# display.net
KiCad netlist of a schematic drawn in EAGLE
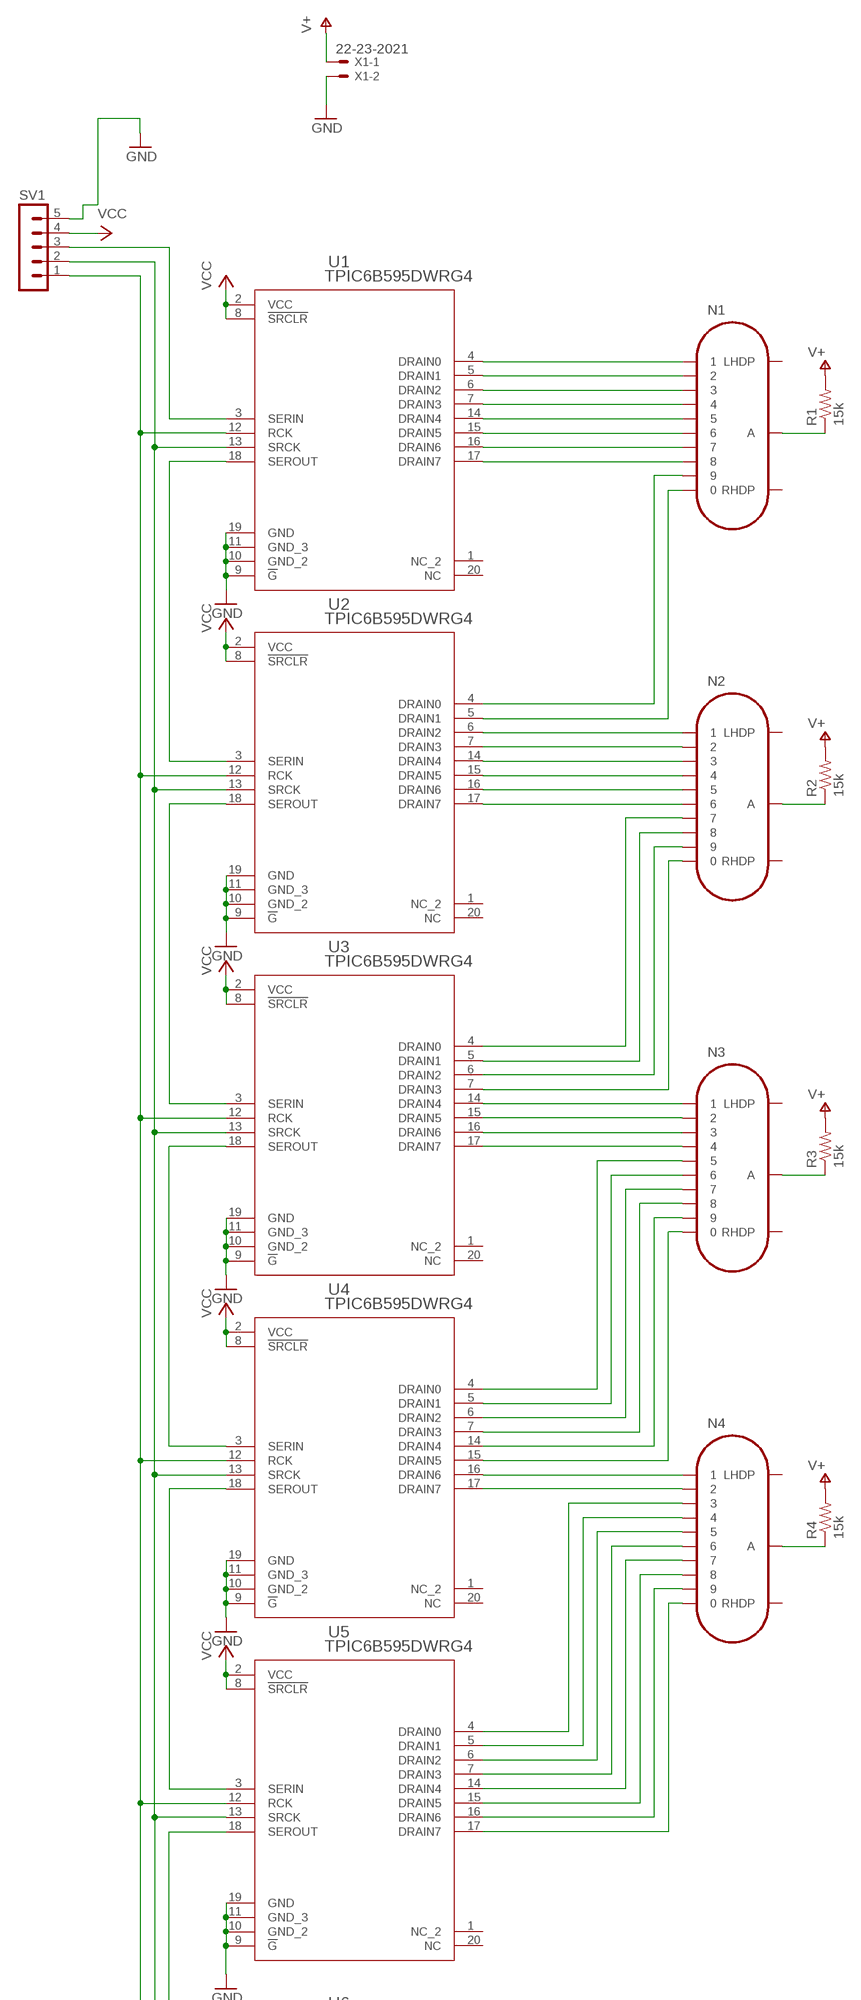
[diagram p0: schematic, sheet 1, part 1 of 2]
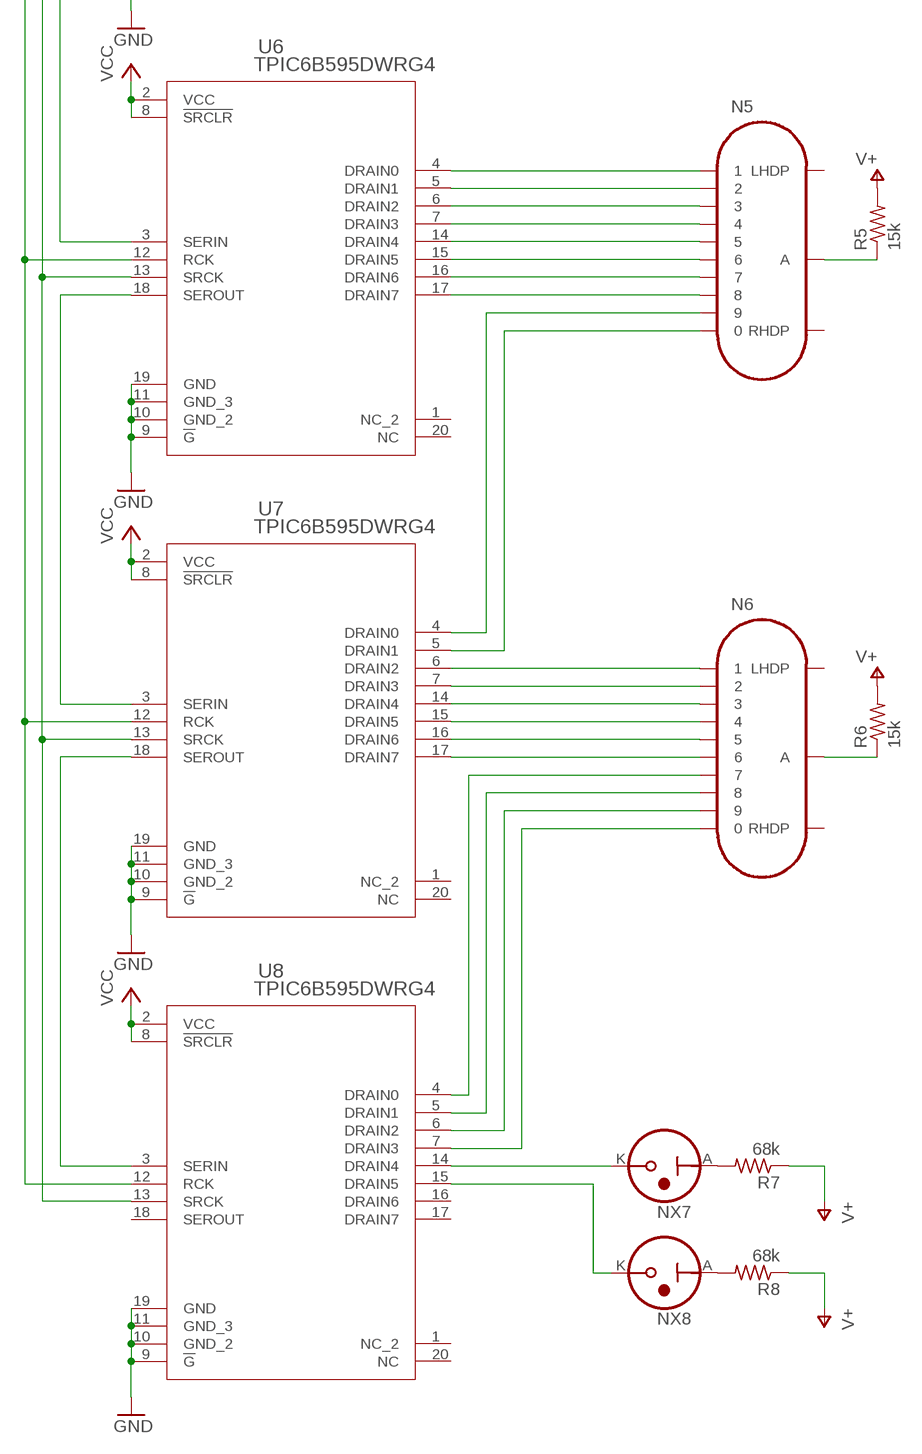
[diagram p1: schematic, sheet 1, part 2 of 2]

(export (version "E")
  (design (tool "Eeschema 10.0.6"))
  (components
    (comp (ref "N1")
      (value "IN-16")
      (footprint "eagle-import:IN-16")
      (libsource (lib "eagle-import") (part "IN-16"))
    )
    (comp (ref "N2")
      (value "IN-16")
      (footprint "eagle-import:IN-16")
      (libsource (lib "eagle-import") (part "IN-16"))
    )
    (comp (ref "N3")
      (value "IN-16")
      (footprint "eagle-import:IN-16")
      (libsource (lib "eagle-import") (part "IN-16"))
    )
    (comp (ref "N4")
      (value "IN-16")
      (footprint "eagle-import:IN-16")
      (libsource (lib "eagle-import") (part "IN-16"))
    )
    (comp (ref "N5")
      (value "IN-16")
      (footprint "eagle-import:IN-16")
      (libsource (lib "eagle-import") (part "IN-16"))
    )
    (comp (ref "N6")
      (value "IN-16")
      (footprint "eagle-import:IN-16")
      (libsource (lib "eagle-import") (part "IN-16"))
    )
    (comp (ref "NX7")
      (value "IN-3")
      (footprint "eagle-import:IN-3")
      (libsource (lib "eagle-import") (part "IN-3"))
    )
    (comp (ref "NX8")
      (value "IN-3")
      (footprint "eagle-import:IN-3")
      (libsource (lib "eagle-import") (part "IN-3"))
    )
    (comp (ref "R1")
      (value "15k")
      (footprint "eagle-import:R0805")
      (libsource (lib "eagle-import") (part "R-US_R0805"))
    )
    (comp (ref "R2")
      (value "15k")
      (footprint "eagle-import:R0805")
      (libsource (lib "eagle-import") (part "R-US_R0805"))
    )
    (comp (ref "R3")
      (value "15k")
      (footprint "eagle-import:R0805")
      (libsource (lib "eagle-import") (part "R-US_R0805"))
    )
    (comp (ref "R4")
      (value "15k")
      (footprint "eagle-import:R0805")
      (libsource (lib "eagle-import") (part "R-US_R0805"))
    )
    (comp (ref "R5")
      (value "15k")
      (footprint "eagle-import:R0805")
      (libsource (lib "eagle-import") (part "R-US_R0805"))
    )
    (comp (ref "R6")
      (value "15k")
      (footprint "eagle-import:R0805")
      (libsource (lib "eagle-import") (part "R-US_R0805"))
    )
    (comp (ref "R7")
      (value "68k")
      (footprint "eagle-import:R0805")
      (libsource (lib "eagle-import") (part "R-US_R0805"))
    )
    (comp (ref "R8")
      (value "68k")
      (footprint "eagle-import:R0805")
      (libsource (lib "eagle-import") (part "R-US_R0805"))
    )
    (comp (ref "SV1")
      (value "MA05-1")
      (footprint "eagle-import:MA05-1")
      (libsource (lib "eagle-import") (part "MA05-1"))
    )
    (comp (ref "U1")
      (value "TPIC6B595DWRG4")
      (footprint "eagle-import:DW20")
      (fields (field (name "MANUFACTURER") "Texas Instruments"))
      (libsource (lib "eagle-import") (part "TPIC6B595DWRG4"))
    )
    (comp (ref "U2")
      (value "TPIC6B595DWRG4")
      (footprint "eagle-import:DW20")
      (fields (field (name "MANUFACTURER") "Texas Instruments"))
      (libsource (lib "eagle-import") (part "TPIC6B595DWRG4"))
    )
    (comp (ref "U3")
      (value "TPIC6B595DWRG4")
      (footprint "eagle-import:DW20")
      (fields (field (name "MANUFACTURER") "Texas Instruments"))
      (libsource (lib "eagle-import") (part "TPIC6B595DWRG4"))
    )
    (comp (ref "U4")
      (value "TPIC6B595DWRG4")
      (footprint "eagle-import:DW20")
      (fields (field (name "MANUFACTURER") "Texas Instruments"))
      (libsource (lib "eagle-import") (part "TPIC6B595DWRG4"))
    )
    (comp (ref "U5")
      (value "TPIC6B595DWRG4")
      (footprint "eagle-import:DW20")
      (fields (field (name "MANUFACTURER") "Texas Instruments"))
      (libsource (lib "eagle-import") (part "TPIC6B595DWRG4"))
    )
    (comp (ref "U6")
      (value "TPIC6B595DWRG4")
      (footprint "eagle-import:DW20")
      (fields (field (name "MANUFACTURER") "Texas Instruments"))
      (libsource (lib "eagle-import") (part "TPIC6B595DWRG4"))
    )
    (comp (ref "U7")
      (value "TPIC6B595DWRG4")
      (footprint "eagle-import:DW20")
      (fields (field (name "MANUFACTURER") "Texas Instruments"))
      (libsource (lib "eagle-import") (part "TPIC6B595DWRG4"))
    )
    (comp (ref "U8")
      (value "TPIC6B595DWRG4")
      (footprint "eagle-import:DW20")
      (fields (field (name "MANUFACTURER") "Texas Instruments"))
      (libsource (lib "eagle-import") (part "TPIC6B595DWRG4"))
    )
    (comp (ref "X1")
      (value "22-23-2021")
      (footprint "eagle-import:22-23-2021")
      (fields (field (name "MF") "MOLEX"))
      (libsource (lib "eagle-import") (part "22-23-2021"))
    )
  )
  (nets
    (net (code "1") (name "GND") (class "Default")
      (node (ref "SV1") (pin "5") (pinfunction "5_5") (pintype "passive"))
      (node (ref "U1") (pin "10") (pinfunction "GND_2_10") (pintype "power_in"))
      (node (ref "U1") (pin "11") (pinfunction "GND_3_11") (pintype "power_in"))
      (node (ref "U1") (pin "19") (pinfunction "GND_19") (pintype "power_in"))
      (node (ref "U1") (pin "9") (pinfunction "~{G}_9") (pintype "input"))
      (node (ref "U2") (pin "10") (pinfunction "GND_2_10") (pintype "power_in"))
      (node (ref "U2") (pin "11") (pinfunction "GND_3_11") (pintype "power_in"))
      (node (ref "U2") (pin "19") (pinfunction "GND_19") (pintype "power_in"))
      (node (ref "U2") (pin "9") (pinfunction "~{G}_9") (pintype "input"))
      (node (ref "U3") (pin "10") (pinfunction "GND_2_10") (pintype "power_in"))
      (node (ref "U3") (pin "11") (pinfunction "GND_3_11") (pintype "power_in"))
      (node (ref "U3") (pin "19") (pinfunction "GND_19") (pintype "power_in"))
      (node (ref "U3") (pin "9") (pinfunction "~{G}_9") (pintype "input"))
      (node (ref "U4") (pin "10") (pinfunction "GND_2_10") (pintype "power_in"))
      (node (ref "U4") (pin "11") (pinfunction "GND_3_11") (pintype "power_in"))
      (node (ref "U4") (pin "19") (pinfunction "GND_19") (pintype "power_in"))
      (node (ref "U4") (pin "9") (pinfunction "~{G}_9") (pintype "input"))
      (node (ref "U5") (pin "10") (pinfunction "GND_2_10") (pintype "power_in"))
      (node (ref "U5") (pin "11") (pinfunction "GND_3_11") (pintype "power_in"))
      (node (ref "U5") (pin "19") (pinfunction "GND_19") (pintype "power_in"))
      (node (ref "U5") (pin "9") (pinfunction "~{G}_9") (pintype "input"))
      (node (ref "U6") (pin "10") (pinfunction "GND_2_10") (pintype "power_in"))
      (node (ref "U6") (pin "11") (pinfunction "GND_3_11") (pintype "power_in"))
      (node (ref "U6") (pin "19") (pinfunction "GND_19") (pintype "power_in"))
      (node (ref "U6") (pin "9") (pinfunction "~{G}_9") (pintype "input"))
      (node (ref "U7") (pin "10") (pinfunction "GND_2_10") (pintype "power_in"))
      (node (ref "U7") (pin "11") (pinfunction "GND_3_11") (pintype "power_in"))
      (node (ref "U7") (pin "19") (pinfunction "GND_19") (pintype "power_in"))
      (node (ref "U7") (pin "9") (pinfunction "~{G}_9") (pintype "input"))
      (node (ref "U8") (pin "10") (pinfunction "GND_2_10") (pintype "power_in"))
      (node (ref "U8") (pin "11") (pinfunction "GND_3_11") (pintype "power_in"))
      (node (ref "U8") (pin "19") (pinfunction "GND_19") (pintype "power_in"))
      (node (ref "U8") (pin "9") (pinfunction "~{G}_9") (pintype "input"))
      (node (ref "X1") (pin "2") (pinfunction "S_2") (pintype "passive"))
    )
    (net (code "2") (name "Net-(N1-PadA)") (class "Default")
      (node (ref "N1") (pin "A") (pinfunction "A_A") (pintype "bidirectional"))
      (node (ref "R1") (pin "1") (pinfunction "1_1") (pintype "passive"))
    )
    (net (code "3") (name "Net-(N2-PadA)") (class "Default")
      (node (ref "N2") (pin "A") (pinfunction "A_A") (pintype "bidirectional"))
      (node (ref "R2") (pin "1") (pinfunction "1_1") (pintype "passive"))
    )
    (net (code "4") (name "Net-(N3-PadA)") (class "Default")
      (node (ref "N3") (pin "A") (pinfunction "A_A") (pintype "bidirectional"))
      (node (ref "R3") (pin "1") (pinfunction "1_1") (pintype "passive"))
    )
    (net (code "5") (name "Net-(N4-PadA)") (class "Default")
      (node (ref "N4") (pin "A") (pinfunction "A_A") (pintype "bidirectional"))
      (node (ref "R4") (pin "1") (pinfunction "1_1") (pintype "passive"))
    )
    (net (code "6") (name "Net-(N5-PadA)") (class "Default")
      (node (ref "N5") (pin "A") (pinfunction "A_A") (pintype "bidirectional"))
      (node (ref "R5") (pin "1") (pinfunction "1_1") (pintype "passive"))
    )
    (net (code "7") (name "Net-(N6-PadA)") (class "Default")
      (node (ref "N6") (pin "A") (pinfunction "A_A") (pintype "bidirectional"))
      (node (ref "R6") (pin "1") (pinfunction "1_1") (pintype "passive"))
    )
    (net (code "8") (name "Net-(NX7-PadA)") (class "Default")
      (node (ref "NX7") (pin "A") (pinfunction "A_A") (pintype "bidirectional"))
      (node (ref "R7") (pin "2") (pinfunction "2_2") (pintype "passive"))
    )
    (net (code "9") (name "Net-(NX8-PadA)") (class "Default")
      (node (ref "NX8") (pin "A") (pinfunction "A_A") (pintype "bidirectional"))
      (node (ref "R8") (pin "2") (pinfunction "2_2") (pintype "passive"))
    )
    (net (code "10") (name "Net-(U1-DRAIN0)") (class "Default")
      (node (ref "N1") (pin "1") (pinfunction "1_1") (pintype "bidirectional"))
      (node (ref "U1") (pin "4") (pinfunction "DRAIN0_4") (pintype "output"))
    )
    (net (code "11") (name "Net-(U1-DRAIN1)") (class "Default")
      (node (ref "N1") (pin "2") (pinfunction "2_2") (pintype "bidirectional"))
      (node (ref "U1") (pin "5") (pinfunction "DRAIN1_5") (pintype "output"))
    )
    (net (code "12") (name "Net-(U1-DRAIN2)") (class "Default")
      (node (ref "N1") (pin "3") (pinfunction "3_3") (pintype "bidirectional"))
      (node (ref "U1") (pin "6") (pinfunction "DRAIN2_6") (pintype "output"))
    )
    (net (code "13") (name "Net-(U1-DRAIN3)") (class "Default")
      (node (ref "N1") (pin "4") (pinfunction "4_4") (pintype "bidirectional"))
      (node (ref "U1") (pin "7") (pinfunction "DRAIN3_7") (pintype "output"))
    )
    (net (code "14") (name "Net-(U1-DRAIN4)") (class "Default")
      (node (ref "N1") (pin "5") (pinfunction "5_5") (pintype "bidirectional"))
      (node (ref "U1") (pin "14") (pinfunction "DRAIN4_14") (pintype "output"))
    )
    (net (code "15") (name "Net-(U1-DRAIN5)") (class "Default")
      (node (ref "N1") (pin "6") (pinfunction "6_6") (pintype "bidirectional"))
      (node (ref "U1") (pin "15") (pinfunction "DRAIN5_15") (pintype "output"))
    )
    (net (code "16") (name "Net-(U1-DRAIN6)") (class "Default")
      (node (ref "N1") (pin "7") (pinfunction "7_7") (pintype "bidirectional"))
      (node (ref "U1") (pin "16") (pinfunction "DRAIN6_16") (pintype "output"))
    )
    (net (code "17") (name "Net-(U1-DRAIN7)") (class "Default")
      (node (ref "N1") (pin "8") (pinfunction "8_8") (pintype "bidirectional"))
      (node (ref "U1") (pin "17") (pinfunction "DRAIN7_17") (pintype "output"))
    )
    (net (code "18") (name "Net-(U1-RCK)") (class "Default")
      (node (ref "SV1") (pin "1") (pinfunction "1_1") (pintype "passive"))
      (node (ref "U1") (pin "12") (pinfunction "RCK_12") (pintype "input"))
      (node (ref "U2") (pin "12") (pinfunction "RCK_12") (pintype "input"))
      (node (ref "U3") (pin "12") (pinfunction "RCK_12") (pintype "input"))
      (node (ref "U4") (pin "12") (pinfunction "RCK_12") (pintype "input"))
      (node (ref "U5") (pin "12") (pinfunction "RCK_12") (pintype "input"))
      (node (ref "U6") (pin "12") (pinfunction "RCK_12") (pintype "input"))
      (node (ref "U7") (pin "12") (pinfunction "RCK_12") (pintype "input"))
      (node (ref "U8") (pin "12") (pinfunction "RCK_12") (pintype "input"))
    )
    (net (code "19") (name "Net-(U1-SERIN)") (class "Default")
      (node (ref "SV1") (pin "3") (pinfunction "3_3") (pintype "passive"))
      (node (ref "U1") (pin "3") (pinfunction "SERIN_3") (pintype "input"))
    )
    (net (code "20") (name "Net-(U1-SEROUT)") (class "Default")
      (node (ref "U1") (pin "18") (pinfunction "SEROUT_18") (pintype "output"))
      (node (ref "U2") (pin "3") (pinfunction "SERIN_3") (pintype "input"))
    )
    (net (code "21") (name "Net-(U1-SRCK)") (class "Default")
      (node (ref "SV1") (pin "2") (pinfunction "2_2") (pintype "passive"))
      (node (ref "U1") (pin "13") (pinfunction "SRCK_13") (pintype "input"))
      (node (ref "U2") (pin "13") (pinfunction "SRCK_13") (pintype "input"))
      (node (ref "U3") (pin "13") (pinfunction "SRCK_13") (pintype "input"))
      (node (ref "U4") (pin "13") (pinfunction "SRCK_13") (pintype "input"))
      (node (ref "U5") (pin "13") (pinfunction "SRCK_13") (pintype "input"))
      (node (ref "U6") (pin "13") (pinfunction "SRCK_13") (pintype "input"))
      (node (ref "U7") (pin "13") (pinfunction "SRCK_13") (pintype "input"))
      (node (ref "U8") (pin "13") (pinfunction "SRCK_13") (pintype "input"))
    )
    (net (code "22") (name "Net-(U2-DRAIN0)") (class "Default")
      (node (ref "N1") (pin "9") (pinfunction "9_9") (pintype "bidirectional"))
      (node (ref "U2") (pin "4") (pinfunction "DRAIN0_4") (pintype "output"))
    )
    (net (code "23") (name "Net-(U2-DRAIN1)") (class "Default")
      (node (ref "N1") (pin "0") (pinfunction "0_0") (pintype "bidirectional"))
      (node (ref "U2") (pin "5") (pinfunction "DRAIN1_5") (pintype "output"))
    )
    (net (code "24") (name "Net-(U2-DRAIN2)") (class "Default")
      (node (ref "N2") (pin "1") (pinfunction "1_1") (pintype "bidirectional"))
      (node (ref "U2") (pin "6") (pinfunction "DRAIN2_6") (pintype "output"))
    )
    (net (code "25") (name "Net-(U2-DRAIN3)") (class "Default")
      (node (ref "N2") (pin "2") (pinfunction "2_2") (pintype "bidirectional"))
      (node (ref "U2") (pin "7") (pinfunction "DRAIN3_7") (pintype "output"))
    )
    (net (code "26") (name "Net-(U2-DRAIN4)") (class "Default")
      (node (ref "N2") (pin "3") (pinfunction "3_3") (pintype "bidirectional"))
      (node (ref "U2") (pin "14") (pinfunction "DRAIN4_14") (pintype "output"))
    )
    (net (code "27") (name "Net-(U2-DRAIN5)") (class "Default")
      (node (ref "N2") (pin "4") (pinfunction "4_4") (pintype "bidirectional"))
      (node (ref "U2") (pin "15") (pinfunction "DRAIN5_15") (pintype "output"))
    )
    (net (code "28") (name "Net-(U2-DRAIN6)") (class "Default")
      (node (ref "N2") (pin "5") (pinfunction "5_5") (pintype "bidirectional"))
      (node (ref "U2") (pin "16") (pinfunction "DRAIN6_16") (pintype "output"))
    )
    (net (code "29") (name "Net-(U2-DRAIN7)") (class "Default")
      (node (ref "N2") (pin "6") (pinfunction "6_6") (pintype "bidirectional"))
      (node (ref "U2") (pin "17") (pinfunction "DRAIN7_17") (pintype "output"))
    )
    (net (code "30") (name "Net-(U2-SEROUT)") (class "Default")
      (node (ref "U2") (pin "18") (pinfunction "SEROUT_18") (pintype "output"))
      (node (ref "U3") (pin "3") (pinfunction "SERIN_3") (pintype "input"))
    )
    (net (code "31") (name "Net-(U3-DRAIN0)") (class "Default")
      (node (ref "N2") (pin "7") (pinfunction "7_7") (pintype "bidirectional"))
      (node (ref "U3") (pin "4") (pinfunction "DRAIN0_4") (pintype "output"))
    )
    (net (code "32") (name "Net-(U3-DRAIN1)") (class "Default")
      (node (ref "N2") (pin "8") (pinfunction "8_8") (pintype "bidirectional"))
      (node (ref "U3") (pin "5") (pinfunction "DRAIN1_5") (pintype "output"))
    )
    (net (code "33") (name "Net-(U3-DRAIN2)") (class "Default")
      (node (ref "N2") (pin "9") (pinfunction "9_9") (pintype "bidirectional"))
      (node (ref "U3") (pin "6") (pinfunction "DRAIN2_6") (pintype "output"))
    )
    (net (code "34") (name "Net-(U3-DRAIN3)") (class "Default")
      (node (ref "N2") (pin "0") (pinfunction "0_0") (pintype "bidirectional"))
      (node (ref "U3") (pin "7") (pinfunction "DRAIN3_7") (pintype "output"))
    )
    (net (code "35") (name "Net-(U3-DRAIN4)") (class "Default")
      (node (ref "N3") (pin "1") (pinfunction "1_1") (pintype "bidirectional"))
      (node (ref "U3") (pin "14") (pinfunction "DRAIN4_14") (pintype "output"))
    )
    (net (code "36") (name "Net-(U3-DRAIN5)") (class "Default")
      (node (ref "N3") (pin "2") (pinfunction "2_2") (pintype "bidirectional"))
      (node (ref "U3") (pin "15") (pinfunction "DRAIN5_15") (pintype "output"))
    )
    (net (code "37") (name "Net-(U3-DRAIN6)") (class "Default")
      (node (ref "N3") (pin "3") (pinfunction "3_3") (pintype "bidirectional"))
      (node (ref "U3") (pin "16") (pinfunction "DRAIN6_16") (pintype "output"))
    )
    (net (code "38") (name "Net-(U3-DRAIN7)") (class "Default")
      (node (ref "N3") (pin "4") (pinfunction "4_4") (pintype "bidirectional"))
      (node (ref "U3") (pin "17") (pinfunction "DRAIN7_17") (pintype "output"))
    )
    (net (code "39") (name "Net-(U3-SEROUT)") (class "Default")
      (node (ref "U3") (pin "18") (pinfunction "SEROUT_18") (pintype "output"))
      (node (ref "U4") (pin "3") (pinfunction "SERIN_3") (pintype "input"))
    )
    (net (code "40") (name "Net-(U4-DRAIN0)") (class "Default")
      (node (ref "N3") (pin "5") (pinfunction "5_5") (pintype "bidirectional"))
      (node (ref "U4") (pin "4") (pinfunction "DRAIN0_4") (pintype "output"))
    )
    (net (code "41") (name "Net-(U4-DRAIN1)") (class "Default")
      (node (ref "N3") (pin "6") (pinfunction "6_6") (pintype "bidirectional"))
      (node (ref "U4") (pin "5") (pinfunction "DRAIN1_5") (pintype "output"))
    )
    (net (code "42") (name "Net-(U4-DRAIN2)") (class "Default")
      (node (ref "N3") (pin "7") (pinfunction "7_7") (pintype "bidirectional"))
      (node (ref "U4") (pin "6") (pinfunction "DRAIN2_6") (pintype "output"))
    )
    (net (code "43") (name "Net-(U4-DRAIN3)") (class "Default")
      (node (ref "N3") (pin "8") (pinfunction "8_8") (pintype "bidirectional"))
      (node (ref "U4") (pin "7") (pinfunction "DRAIN3_7") (pintype "output"))
    )
    (net (code "44") (name "Net-(U4-DRAIN4)") (class "Default")
      (node (ref "N3") (pin "9") (pinfunction "9_9") (pintype "bidirectional"))
      (node (ref "U4") (pin "14") (pinfunction "DRAIN4_14") (pintype "output"))
    )
    (net (code "45") (name "Net-(U4-DRAIN5)") (class "Default")
      (node (ref "N3") (pin "0") (pinfunction "0_0") (pintype "bidirectional"))
      (node (ref "U4") (pin "15") (pinfunction "DRAIN5_15") (pintype "output"))
    )
    (net (code "46") (name "Net-(U4-DRAIN6)") (class "Default")
      (node (ref "N4") (pin "1") (pinfunction "1_1") (pintype "bidirectional"))
      (node (ref "U4") (pin "16") (pinfunction "DRAIN6_16") (pintype "output"))
    )
    (net (code "47") (name "Net-(U4-DRAIN7)") (class "Default")
      (node (ref "N4") (pin "2") (pinfunction "2_2") (pintype "bidirectional"))
      (node (ref "U4") (pin "17") (pinfunction "DRAIN7_17") (pintype "output"))
    )
    (net (code "48") (name "Net-(U4-SEROUT)") (class "Default")
      (node (ref "U4") (pin "18") (pinfunction "SEROUT_18") (pintype "output"))
      (node (ref "U5") (pin "3") (pinfunction "SERIN_3") (pintype "input"))
    )
    (net (code "49") (name "Net-(U5-DRAIN0)") (class "Default")
      (node (ref "N4") (pin "3") (pinfunction "3_3") (pintype "bidirectional"))
      (node (ref "U5") (pin "4") (pinfunction "DRAIN0_4") (pintype "output"))
    )
    (net (code "50") (name "Net-(U5-DRAIN1)") (class "Default")
      (node (ref "N4") (pin "4") (pinfunction "4_4") (pintype "bidirectional"))
      (node (ref "U5") (pin "5") (pinfunction "DRAIN1_5") (pintype "output"))
    )
    (net (code "51") (name "Net-(U5-DRAIN2)") (class "Default")
      (node (ref "N4") (pin "5") (pinfunction "5_5") (pintype "bidirectional"))
      (node (ref "U5") (pin "6") (pinfunction "DRAIN2_6") (pintype "output"))
    )
    (net (code "52") (name "Net-(U5-DRAIN3)") (class "Default")
      (node (ref "N4") (pin "6") (pinfunction "6_6") (pintype "bidirectional"))
      (node (ref "U5") (pin "7") (pinfunction "DRAIN3_7") (pintype "output"))
    )
    (net (code "53") (name "Net-(U5-DRAIN4)") (class "Default")
      (node (ref "N4") (pin "7") (pinfunction "7_7") (pintype "bidirectional"))
      (node (ref "U5") (pin "14") (pinfunction "DRAIN4_14") (pintype "output"))
    )
    (net (code "54") (name "Net-(U5-DRAIN5)") (class "Default")
      (node (ref "N4") (pin "8") (pinfunction "8_8") (pintype "bidirectional"))
      (node (ref "U5") (pin "15") (pinfunction "DRAIN5_15") (pintype "output"))
    )
    (net (code "55") (name "Net-(U5-DRAIN6)") (class "Default")
      (node (ref "N4") (pin "9") (pinfunction "9_9") (pintype "bidirectional"))
      (node (ref "U5") (pin "16") (pinfunction "DRAIN6_16") (pintype "output"))
    )
    (net (code "56") (name "Net-(U5-DRAIN7)") (class "Default")
      (node (ref "N4") (pin "0") (pinfunction "0_0") (pintype "bidirectional"))
      (node (ref "U5") (pin "17") (pinfunction "DRAIN7_17") (pintype "output"))
    )
    (net (code "57") (name "Net-(U5-SEROUT)") (class "Default")
      (node (ref "U5") (pin "18") (pinfunction "SEROUT_18") (pintype "output"))
      (node (ref "U6") (pin "3") (pinfunction "SERIN_3") (pintype "input"))
    )
    (net (code "58") (name "Net-(U6-DRAIN0)") (class "Default")
      (node (ref "N5") (pin "1") (pinfunction "1_1") (pintype "bidirectional"))
      (node (ref "U6") (pin "4") (pinfunction "DRAIN0_4") (pintype "output"))
    )
    (net (code "59") (name "Net-(U6-DRAIN1)") (class "Default")
      (node (ref "N5") (pin "2") (pinfunction "2_2") (pintype "bidirectional"))
      (node (ref "U6") (pin "5") (pinfunction "DRAIN1_5") (pintype "output"))
    )
    (net (code "60") (name "Net-(U6-DRAIN2)") (class "Default")
      (node (ref "N5") (pin "3") (pinfunction "3_3") (pintype "bidirectional"))
      (node (ref "U6") (pin "6") (pinfunction "DRAIN2_6") (pintype "output"))
    )
    (net (code "61") (name "Net-(U6-DRAIN3)") (class "Default")
      (node (ref "N5") (pin "4") (pinfunction "4_4") (pintype "bidirectional"))
      (node (ref "U6") (pin "7") (pinfunction "DRAIN3_7") (pintype "output"))
    )
    (net (code "62") (name "Net-(U6-DRAIN4)") (class "Default")
      (node (ref "N5") (pin "5") (pinfunction "5_5") (pintype "bidirectional"))
      (node (ref "U6") (pin "14") (pinfunction "DRAIN4_14") (pintype "output"))
    )
    (net (code "63") (name "Net-(U6-DRAIN5)") (class "Default")
      (node (ref "N5") (pin "6") (pinfunction "6_6") (pintype "bidirectional"))
      (node (ref "U6") (pin "15") (pinfunction "DRAIN5_15") (pintype "output"))
    )
    (net (code "64") (name "Net-(U6-DRAIN6)") (class "Default")
      (node (ref "N5") (pin "7") (pinfunction "7_7") (pintype "bidirectional"))
      (node (ref "U6") (pin "16") (pinfunction "DRAIN6_16") (pintype "output"))
    )
    (net (code "65") (name "Net-(U6-DRAIN7)") (class "Default")
      (node (ref "N5") (pin "8") (pinfunction "8_8") (pintype "bidirectional"))
      (node (ref "U6") (pin "17") (pinfunction "DRAIN7_17") (pintype "output"))
    )
    (net (code "66") (name "Net-(U6-SEROUT)") (class "Default")
      (node (ref "U6") (pin "18") (pinfunction "SEROUT_18") (pintype "output"))
      (node (ref "U7") (pin "3") (pinfunction "SERIN_3") (pintype "input"))
    )
    (net (code "67") (name "Net-(U7-DRAIN0)") (class "Default")
      (node (ref "N5") (pin "9") (pinfunction "9_9") (pintype "bidirectional"))
      (node (ref "U7") (pin "4") (pinfunction "DRAIN0_4") (pintype "output"))
    )
    (net (code "68") (name "Net-(U7-DRAIN1)") (class "Default")
      (node (ref "N5") (pin "0") (pinfunction "0_0") (pintype "bidirectional"))
      (node (ref "U7") (pin "5") (pinfunction "DRAIN1_5") (pintype "output"))
    )
    (net (code "69") (name "Net-(U7-DRAIN2)") (class "Default")
      (node (ref "N6") (pin "1") (pinfunction "1_1") (pintype "bidirectional"))
      (node (ref "U7") (pin "6") (pinfunction "DRAIN2_6") (pintype "output"))
    )
    (net (code "70") (name "Net-(U7-DRAIN3)") (class "Default")
      (node (ref "N6") (pin "2") (pinfunction "2_2") (pintype "bidirectional"))
      (node (ref "U7") (pin "7") (pinfunction "DRAIN3_7") (pintype "output"))
    )
    (net (code "71") (name "Net-(U7-DRAIN4)") (class "Default")
      (node (ref "N6") (pin "3") (pinfunction "3_3") (pintype "bidirectional"))
      (node (ref "U7") (pin "14") (pinfunction "DRAIN4_14") (pintype "output"))
    )
    (net (code "72") (name "Net-(U7-DRAIN5)") (class "Default")
      (node (ref "N6") (pin "4") (pinfunction "4_4") (pintype "bidirectional"))
      (node (ref "U7") (pin "15") (pinfunction "DRAIN5_15") (pintype "output"))
    )
    (net (code "73") (name "Net-(U7-DRAIN6)") (class "Default")
      (node (ref "N6") (pin "5") (pinfunction "5_5") (pintype "bidirectional"))
      (node (ref "U7") (pin "16") (pinfunction "DRAIN6_16") (pintype "output"))
    )
    (net (code "74") (name "Net-(U7-DRAIN7)") (class "Default")
      (node (ref "N6") (pin "6") (pinfunction "6_6") (pintype "bidirectional"))
      (node (ref "U7") (pin "17") (pinfunction "DRAIN7_17") (pintype "output"))
    )
    (net (code "75") (name "Net-(U7-SEROUT)") (class "Default")
      (node (ref "U7") (pin "18") (pinfunction "SEROUT_18") (pintype "output"))
      (node (ref "U8") (pin "3") (pinfunction "SERIN_3") (pintype "input"))
    )
    (net (code "76") (name "Net-(U8-DRAIN0)") (class "Default")
      (node (ref "N6") (pin "7") (pinfunction "7_7") (pintype "bidirectional"))
      (node (ref "U8") (pin "4") (pinfunction "DRAIN0_4") (pintype "output"))
    )
    (net (code "77") (name "Net-(U8-DRAIN1)") (class "Default")
      (node (ref "N6") (pin "8") (pinfunction "8_8") (pintype "bidirectional"))
      (node (ref "U8") (pin "5") (pinfunction "DRAIN1_5") (pintype "output"))
    )
    (net (code "78") (name "Net-(U8-DRAIN2)") (class "Default")
      (node (ref "N6") (pin "9") (pinfunction "9_9") (pintype "bidirectional"))
      (node (ref "U8") (pin "6") (pinfunction "DRAIN2_6") (pintype "output"))
    )
    (net (code "79") (name "Net-(U8-DRAIN3)") (class "Default")
      (node (ref "N6") (pin "0") (pinfunction "0_0") (pintype "bidirectional"))
      (node (ref "U8") (pin "7") (pinfunction "DRAIN3_7") (pintype "output"))
    )
    (net (code "80") (name "Net-(U8-DRAIN4)") (class "Default")
      (node (ref "NX7") (pin "K") (pinfunction "K_K") (pintype "bidirectional"))
      (node (ref "U8") (pin "14") (pinfunction "DRAIN4_14") (pintype "output"))
    )
    (net (code "81") (name "Net-(U8-DRAIN5)") (class "Default")
      (node (ref "NX8") (pin "K") (pinfunction "K_K") (pintype "bidirectional"))
      (node (ref "U8") (pin "15") (pinfunction "DRAIN5_15") (pintype "output"))
    )
    (net (code "82") (name "V+") (class "Default")
      (node (ref "R1") (pin "2") (pinfunction "2_2") (pintype "passive"))
      (node (ref "R2") (pin "2") (pinfunction "2_2") (pintype "passive"))
      (node (ref "R3") (pin "2") (pinfunction "2_2") (pintype "passive"))
      (node (ref "R4") (pin "2") (pinfunction "2_2") (pintype "passive"))
      (node (ref "R5") (pin "2") (pinfunction "2_2") (pintype "passive"))
      (node (ref "R6") (pin "2") (pinfunction "2_2") (pintype "passive"))
      (node (ref "R7") (pin "1") (pinfunction "1_1") (pintype "passive"))
      (node (ref "R8") (pin "1") (pinfunction "1_1") (pintype "passive"))
      (node (ref "X1") (pin "1") (pinfunction "S_1") (pintype "passive"))
    )
    (net (code "83") (name "VCC") (class "Default")
      (node (ref "SV1") (pin "4") (pinfunction "4_4") (pintype "passive"))
      (node (ref "U1") (pin "2") (pinfunction "VCC_2") (pintype "power_in"))
      (node (ref "U1") (pin "8") (pinfunction "~{SRCLR}_8") (pintype "input"))
      (node (ref "U2") (pin "2") (pinfunction "VCC_2") (pintype "power_in"))
      (node (ref "U2") (pin "8") (pinfunction "~{SRCLR}_8") (pintype "input"))
      (node (ref "U3") (pin "2") (pinfunction "VCC_2") (pintype "power_in"))
      (node (ref "U3") (pin "8") (pinfunction "~{SRCLR}_8") (pintype "input"))
      (node (ref "U4") (pin "2") (pinfunction "VCC_2") (pintype "power_in"))
      (node (ref "U4") (pin "8") (pinfunction "~{SRCLR}_8") (pintype "input"))
      (node (ref "U5") (pin "2") (pinfunction "VCC_2") (pintype "power_in"))
      (node (ref "U5") (pin "8") (pinfunction "~{SRCLR}_8") (pintype "input"))
      (node (ref "U6") (pin "2") (pinfunction "VCC_2") (pintype "power_in"))
      (node (ref "U6") (pin "8") (pinfunction "~{SRCLR}_8") (pintype "input"))
      (node (ref "U7") (pin "2") (pinfunction "VCC_2") (pintype "power_in"))
      (node (ref "U7") (pin "8") (pinfunction "~{SRCLR}_8") (pintype "input"))
      (node (ref "U8") (pin "2") (pinfunction "VCC_2") (pintype "power_in"))
      (node (ref "U8") (pin "8") (pinfunction "~{SRCLR}_8") (pintype "input"))
    )
    (net (code "84") (name "unconnected-(N1-PadLHDP)") (class "Default")
      (node (ref "N1") (pin "LHDP") (pinfunction "LHDP_LHDP") (pintype "bidirectional"))
    )
    (net (code "85") (name "unconnected-(N1-PadRHDP)") (class "Default")
      (node (ref "N1") (pin "RHDP") (pinfunction "RHDP_RHDP") (pintype "bidirectional"))
    )
    (net (code "86") (name "unconnected-(N2-PadLHDP)") (class "Default")
      (node (ref "N2") (pin "LHDP") (pinfunction "LHDP_LHDP") (pintype "bidirectional"))
    )
    (net (code "87") (name "unconnected-(N2-PadRHDP)") (class "Default")
      (node (ref "N2") (pin "RHDP") (pinfunction "RHDP_RHDP") (pintype "bidirectional"))
    )
    (net (code "88") (name "unconnected-(N3-PadLHDP)") (class "Default")
      (node (ref "N3") (pin "LHDP") (pinfunction "LHDP_LHDP") (pintype "bidirectional"))
    )
    (net (code "89") (name "unconnected-(N3-PadRHDP)") (class "Default")
      (node (ref "N3") (pin "RHDP") (pinfunction "RHDP_RHDP") (pintype "bidirectional"))
    )
    (net (code "90") (name "unconnected-(N4-PadLHDP)") (class "Default")
      (node (ref "N4") (pin "LHDP") (pinfunction "LHDP_LHDP") (pintype "bidirectional"))
    )
    (net (code "91") (name "unconnected-(N4-PadRHDP)") (class "Default")
      (node (ref "N4") (pin "RHDP") (pinfunction "RHDP_RHDP") (pintype "bidirectional"))
    )
    (net (code "92") (name "unconnected-(N5-PadLHDP)") (class "Default")
      (node (ref "N5") (pin "LHDP") (pinfunction "LHDP_LHDP") (pintype "bidirectional"))
    )
    (net (code "93") (name "unconnected-(N5-PadRHDP)") (class "Default")
      (node (ref "N5") (pin "RHDP") (pinfunction "RHDP_RHDP") (pintype "bidirectional"))
    )
    (net (code "94") (name "unconnected-(N6-PadLHDP)") (class "Default")
      (node (ref "N6") (pin "LHDP") (pinfunction "LHDP_LHDP") (pintype "bidirectional"))
    )
    (net (code "95") (name "unconnected-(N6-PadRHDP)") (class "Default")
      (node (ref "N6") (pin "RHDP") (pinfunction "RHDP_RHDP") (pintype "bidirectional"))
    )
    (net (code "96") (name "unconnected-(U1-NC-Pad20)") (class "Default")
      (node (ref "U1") (pin "20") (pinfunction "NC_20") (pintype "passive"))
    )
    (net (code "97") (name "unconnected-(U1-NC_2-Pad1)") (class "Default")
      (node (ref "U1") (pin "1") (pinfunction "NC_2_1") (pintype "passive"))
    )
    (net (code "98") (name "unconnected-(U2-NC-Pad20)") (class "Default")
      (node (ref "U2") (pin "20") (pinfunction "NC_20") (pintype "passive"))
    )
    (net (code "99") (name "unconnected-(U2-NC_2-Pad1)") (class "Default")
      (node (ref "U2") (pin "1") (pinfunction "NC_2_1") (pintype "passive"))
    )
    (net (code "100") (name "unconnected-(U3-NC-Pad20)") (class "Default")
      (node (ref "U3") (pin "20") (pinfunction "NC_20") (pintype "passive"))
    )
    (net (code "101") (name "unconnected-(U3-NC_2-Pad1)") (class "Default")
      (node (ref "U3") (pin "1") (pinfunction "NC_2_1") (pintype "passive"))
    )
    (net (code "102") (name "unconnected-(U4-NC-Pad20)") (class "Default")
      (node (ref "U4") (pin "20") (pinfunction "NC_20") (pintype "passive"))
    )
    (net (code "103") (name "unconnected-(U4-NC_2-Pad1)") (class "Default")
      (node (ref "U4") (pin "1") (pinfunction "NC_2_1") (pintype "passive"))
    )
    (net (code "104") (name "unconnected-(U5-NC-Pad20)") (class "Default")
      (node (ref "U5") (pin "20") (pinfunction "NC_20") (pintype "passive"))
    )
    (net (code "105") (name "unconnected-(U5-NC_2-Pad1)") (class "Default")
      (node (ref "U5") (pin "1") (pinfunction "NC_2_1") (pintype "passive"))
    )
    (net (code "106") (name "unconnected-(U6-NC-Pad20)") (class "Default")
      (node (ref "U6") (pin "20") (pinfunction "NC_20") (pintype "passive"))
    )
    (net (code "107") (name "unconnected-(U6-NC_2-Pad1)") (class "Default")
      (node (ref "U6") (pin "1") (pinfunction "NC_2_1") (pintype "passive"))
    )
    (net (code "108") (name "unconnected-(U7-NC-Pad20)") (class "Default")
      (node (ref "U7") (pin "20") (pinfunction "NC_20") (pintype "passive"))
    )
    (net (code "109") (name "unconnected-(U7-NC_2-Pad1)") (class "Default")
      (node (ref "U7") (pin "1") (pinfunction "NC_2_1") (pintype "passive"))
    )
    (net (code "110") (name "unconnected-(U8-DRAIN6-Pad16)") (class "Default")
      (node (ref "U8") (pin "16") (pinfunction "DRAIN6_16") (pintype "output"))
    )
    (net (code "111") (name "unconnected-(U8-DRAIN7-Pad17)") (class "Default")
      (node (ref "U8") (pin "17") (pinfunction "DRAIN7_17") (pintype "output"))
    )
    (net (code "112") (name "unconnected-(U8-NC-Pad20)") (class "Default")
      (node (ref "U8") (pin "20") (pinfunction "NC_20") (pintype "passive"))
    )
    (net (code "113") (name "unconnected-(U8-NC_2-Pad1)") (class "Default")
      (node (ref "U8") (pin "1") (pinfunction "NC_2_1") (pintype "passive"))
    )
    (net (code "114") (name "unconnected-(U8-SEROUT-Pad18)") (class "Default")
      (node (ref "U8") (pin "18") (pinfunction "SEROUT_18") (pintype "output"))
    )
  )
)
